# 02.net
KiCad netlist of a schematic drawn in Altium Designer
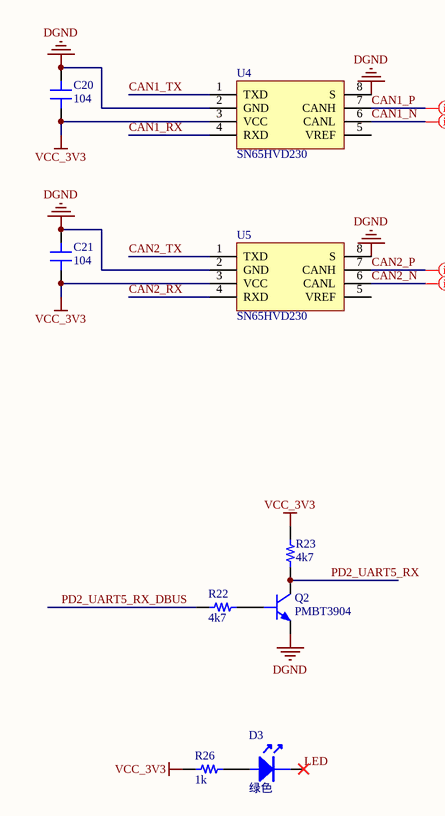
[diagram p0: 02_其它.SchDoc]

(export (version "E")
  (design (tool "Eeschema 10.0.6"))
  (components
    (comp (ref "C20")
      (value "104")
      (footprint "C0603/1608")
      (description "陶瓷电容")
      (libsource (lib "WMJ2019_Devices") (part "陶瓷电容"))
    )
    (comp (ref "C21")
      (value "104")
      (footprint "C0603/1608")
      (description "陶瓷电容")
      (libsource (lib "WMJ2019_Devices") (part "陶瓷电容"))
    )
    (comp (ref "D3")
      (value "LED-绿色")
      (footprint "LED0603-绿色")
      (description "发光二极管")
      (fields (field (name "COLOR") "绿色"))
      (libsource (lib "WMJ2019_Devices") (part "LED"))
    )
    (comp (ref "Q2")
      (value "PMBT3904")
      (footprint "SOT-23-3")
      (description "NPN三极管")
      (fields (field (name "PUBLISHER") "Altium Limited"))
      (libsource (lib "WMJ2019_Devices") (part "NPN"))
    )
    (comp (ref "R22")
      (value "4k7")
      (footprint "R0603/1608")
      (description "电阻")
      (libsource (lib "WMJ2019_Devices") (part "电阻"))
    )
    (comp (ref "R23")
      (value "4k7")
      (footprint "R0603/1608")
      (description "电阻")
      (libsource (lib "WMJ2019_Devices") (part "电阻"))
    )
    (comp (ref "R26")
      (value "1k")
      (footprint "R0603/1608")
      (description "电阻")
      (libsource (lib "WMJ2019_Devices") (part "电阻"))
    )
    (comp (ref "U4")
      (value "SN65HVD230")
      (footprint "SOP-8")
      (description "CAN收发芯片")
      (libsource (lib "WMJ2019_Devices") (part "SN65HVD230"))
    )
    (comp (ref "U5")
      (value "SN65HVD230")
      (footprint "SOP-8")
      (description "CAN收发芯片")
      (libsource (lib "WMJ2019_Devices") (part "SN65HVD230"))
    )
  )
  (nets
    (net (code "1") (name "/CAN1_N") (class "Default")
      (node (ref "U4") (pin "6") (pinfunction "CANL_6") (pintype "passive"))
    )
    (net (code "2") (name "/CAN1_P") (class "Default")
      (node (ref "U4") (pin "7") (pinfunction "CANH_7") (pintype "passive"))
    )
    (net (code "3") (name "/CAN1_RX") (class "Default")
      (node (ref "U4") (pin "4") (pinfunction "RXD_4") (pintype "passive"))
    )
    (net (code "4") (name "/CAN1_TX") (class "Default")
      (node (ref "U4") (pin "1") (pinfunction "TXD_1") (pintype "passive"))
    )
    (net (code "5") (name "/CAN2_N") (class "Default")
      (node (ref "U5") (pin "6") (pinfunction "CANL_6") (pintype "passive"))
    )
    (net (code "6") (name "/CAN2_P") (class "Default")
      (node (ref "U5") (pin "7") (pinfunction "CANH_7") (pintype "passive"))
    )
    (net (code "7") (name "/CAN2_RX") (class "Default")
      (node (ref "U5") (pin "4") (pinfunction "RXD_4") (pintype "passive"))
    )
    (net (code "8") (name "/CAN2_TX") (class "Default")
      (node (ref "U5") (pin "1") (pinfunction "TXD_1") (pintype "passive"))
    )
    (net (code "9") (name "/LED") (class "Default")
      (node (ref "D3") (pin "2") (pinfunction "K_2") (pintype "passive+no_connect"))
    )
    (net (code "10") (name "/PD2_UART5_RX") (class "Default")
      (node (ref "Q2") (pin "3") (pinfunction "C_3") (pintype "passive"))
      (node (ref "R23") (pin "2") (pintype "passive"))
    )
    (net (code "11") (name "/PD2_UART5_RX_DBUS") (class "Default")
      (node (ref "R22") (pin "2") (pintype "passive"))
    )
    (net (code "12") (name "DGND") (class "Default")
      (node (ref "C20") (pin "2") (pintype "passive"))
      (node (ref "C21") (pin "2") (pintype "passive"))
      (node (ref "Q2") (pin "2") (pinfunction "E_2") (pintype "passive"))
      (node (ref "U4") (pin "2") (pinfunction "GND_2") (pintype "passive"))
      (node (ref "U4") (pin "8") (pinfunction "S_8") (pintype "passive"))
      (node (ref "U5") (pin "2") (pinfunction "GND_2") (pintype "passive"))
      (node (ref "U5") (pin "8") (pinfunction "S_8") (pintype "passive"))
    )
    (net (code "13") (name "Net-(D3-A)") (class "Default")
      (node (ref "D3") (pin "1") (pinfunction "A_1") (pintype "passive"))
      (node (ref "R26") (pin "1") (pintype "passive"))
    )
    (net (code "14") (name "Net-(Q2-B)") (class "Default")
      (node (ref "Q2") (pin "1") (pinfunction "B_1") (pintype "passive"))
      (node (ref "R22") (pin "1") (pintype "passive"))
    )
    (net (code "15") (name "VCC_3V3") (class "Default")
      (node (ref "C20") (pin "1") (pintype "passive"))
      (node (ref "C21") (pin "1") (pintype "passive"))
      (node (ref "R23") (pin "1") (pintype "passive"))
      (node (ref "R26") (pin "2") (pintype "passive"))
      (node (ref "U4") (pin "3") (pinfunction "VCC_3") (pintype "passive"))
      (node (ref "U5") (pin "3") (pinfunction "VCC_3") (pintype "passive"))
    )
    (net (code "16") (name "unconnected-(U4-VREF-Pad5)") (class "Default")
      (node (ref "U4") (pin "5") (pinfunction "VREF_5") (pintype "passive"))
    )
    (net (code "17") (name "unconnected-(U5-VREF-Pad5)") (class "Default")
      (node (ref "U5") (pin "5") (pinfunction "VREF_5") (pintype "passive"))
    )
  )
)
